# 5_Analog.net
KiCad netlist of a schematic drawn in Altium Designer
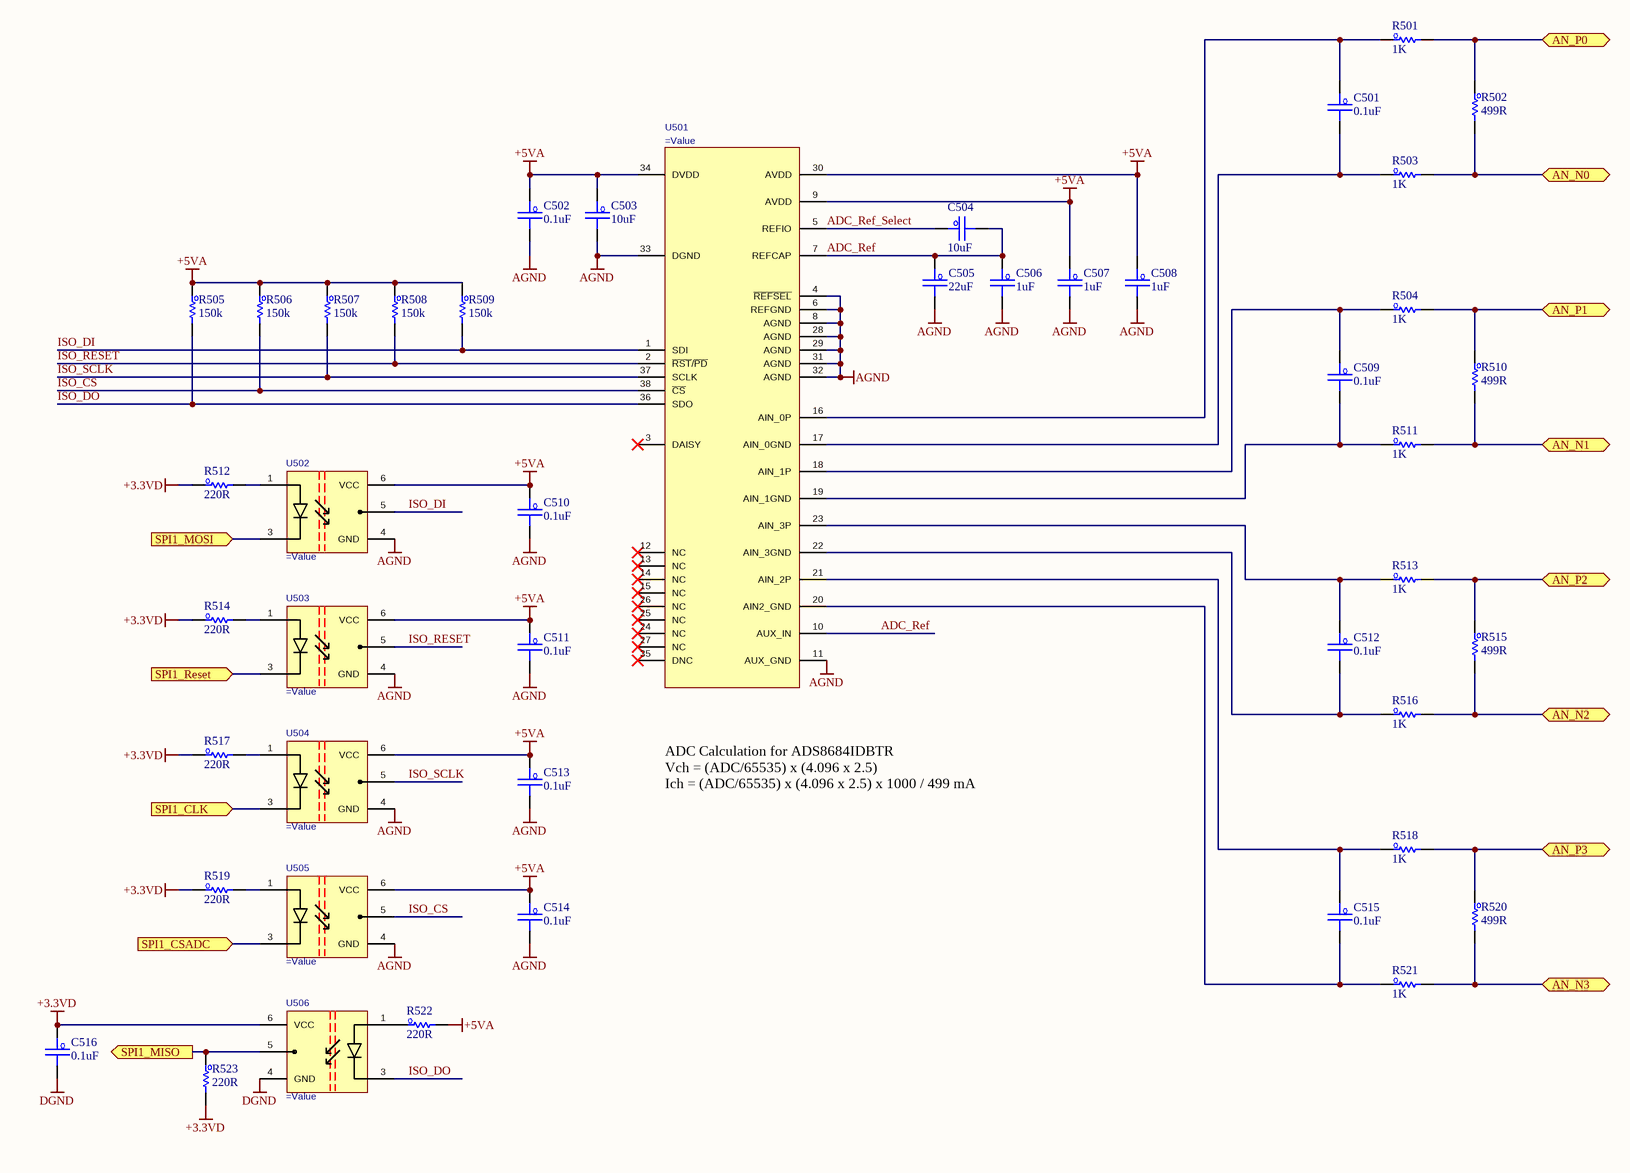
[diagram p0: 5_Analog.SchDoc]

(export (version "E")
  (design (tool "Eeschema 10.0.6"))
  (components
    (comp (ref "C501")
      (value "0.1uF")
      (footprint "C_0603")
      (description "CAP CER 0.1UF 50V X7R 0603")
      (fields (field (name "MANUFACTURER") "KEMET") (field (name "PARTNUMBER") "C0603C104K5RACTU"))
      (libsource (lib "UUSymbol") (part "C_Capacitor"))
    )
    (comp (ref "C502")
      (value "0.1uF")
      (footprint "C_0603")
      (description "CAP CER 0.1UF 50V X7R 0603")
      (fields (field (name "MANUFACTURER") "KEMET") (field (name "PARTNUMBER") "C0603C104K5RACTU"))
      (libsource (lib "UUSymbol") (part "C_Capacitor"))
    )
    (comp (ref "C503")
      (value "10uF")
      (footprint "C_0603")
      (description "CAP CER 10UF 10V X6S 0603")
      (fields
        (field (name "MANUFACTURER") "Murata Electronics")
        (field (name "PARTNUMBER") "GRT188C81A106ME13D")
      )
      (libsource (lib "UUSymbol") (part "C_Capacitor"))
    )
    (comp (ref "C504")
      (value "10uF")
      (footprint "C_0603")
      (description "CAP CER 10UF 10V X6S 0603")
      (fields
        (field (name "MANUFACTURER") "Murata Electronics")
        (field (name "PARTNUMBER") "GRT188C81A106ME13D")
      )
      (libsource (lib "UUSymbol") (part "C_Capacitor"))
    )
    (comp (ref "C505")
      (value "22uF")
      (footprint "C_0603")
      (description "CAP CER 22UF 10V X5R 0603")
      (fields
        (field (name "MANUFACTURER") "Murata Electronics")
        (field (name "PARTNUMBER") "GRM187R61A226ME15D")
      )
      (libsource (lib "UUSymbol") (part "C_Capacitor"))
    )
    (comp (ref "C506")
      (value "1uF")
      (footprint "C_0603")
      (description "CAP CER 1UF 50V X5R 0603")
      (fields
        (field (name "MANUFACTURER") "Murata Electronics")
        (field (name "PARTNUMBER") "GRT188R61H105KE13D")
      )
      (libsource (lib "UUSymbol") (part "C_Capacitor"))
    )
    (comp (ref "C507")
      (value "1uF")
      (footprint "C_0603")
      (description "CAP CER 1UF 50V X5R 0603")
      (fields
        (field (name "MANUFACTURER") "Murata Electronics")
        (field (name "PARTNUMBER") "GRT188R61H105KE13D")
      )
      (libsource (lib "UUSymbol") (part "C_Capacitor"))
    )
    (comp (ref "C508")
      (value "1uF")
      (footprint "C_0603")
      (description "CAP CER 1UF 50V X5R 0603")
      (fields
        (field (name "MANUFACTURER") "Murata Electronics")
        (field (name "PARTNUMBER") "GRT188R61H105KE13D")
      )
      (libsource (lib "UUSymbol") (part "C_Capacitor"))
    )
    (comp (ref "C509")
      (value "0.1uF")
      (footprint "C_0603")
      (description "CAP CER 0.1UF 50V X7R 0603")
      (fields (field (name "MANUFACTURER") "KEMET") (field (name "PARTNUMBER") "C0603C104K5RACTU"))
      (libsource (lib "UUSymbol") (part "C_Capacitor"))
    )
    (comp (ref "C510")
      (value "0.1uF")
      (footprint "C_0603")
      (description "CAP CER 0.1UF 50V X7R 0603")
      (fields (field (name "MANUFACTURER") "KEMET") (field (name "PARTNUMBER") "C0603C104K5RACTU"))
      (libsource (lib "UUSymbol") (part "C_Capacitor"))
    )
    (comp (ref "C511")
      (value "0.1uF")
      (footprint "C_0603")
      (description "CAP CER 0.1UF 50V X7R 0603")
      (fields (field (name "MANUFACTURER") "KEMET") (field (name "PARTNUMBER") "C0603C104K5RACTU"))
      (libsource (lib "UUSymbol") (part "C_Capacitor"))
    )
    (comp (ref "C512")
      (value "0.1uF")
      (footprint "C_0603")
      (description "CAP CER 0.1UF 50V X7R 0603")
      (fields (field (name "MANUFACTURER") "KEMET") (field (name "PARTNUMBER") "C0603C104K5RACTU"))
      (libsource (lib "UUSymbol") (part "C_Capacitor"))
    )
    (comp (ref "C513")
      (value "0.1uF")
      (footprint "C_0603")
      (description "CAP CER 0.1UF 50V X7R 0603")
      (fields (field (name "MANUFACTURER") "KEMET") (field (name "PARTNUMBER") "C0603C104K5RACTU"))
      (libsource (lib "UUSymbol") (part "C_Capacitor"))
    )
    (comp (ref "C514")
      (value "0.1uF")
      (footprint "C_0603")
      (description "CAP CER 0.1UF 50V X7R 0603")
      (fields (field (name "MANUFACTURER") "KEMET") (field (name "PARTNUMBER") "C0603C104K5RACTU"))
      (libsource (lib "UUSymbol") (part "C_Capacitor"))
    )
    (comp (ref "C515")
      (value "0.1uF")
      (footprint "C_0603")
      (description "CAP CER 0.1UF 50V X7R 0603")
      (fields (field (name "MANUFACTURER") "KEMET") (field (name "PARTNUMBER") "C0603C104K5RACTU"))
      (libsource (lib "UUSymbol") (part "C_Capacitor"))
    )
    (comp (ref "C516")
      (value "0.1uF")
      (footprint "C_0603")
      (description "CAP CER 0.1UF 50V X7R 0603")
      (fields (field (name "MANUFACTURER") "KEMET") (field (name "PARTNUMBER") "C0603C104K5RACTU"))
      (libsource (lib "UUSymbol") (part "C_Capacitor"))
    )
    (comp (ref "R501")
      (value "1K")
      (footprint "R_0603")
      (description "RES SMD 1K OHM 5% 1/10W 0603")
      (fields (field (name "MANUFACTURER") "Vishay Dale") (field (name "PARTNUMBER") "CRCW06031K00JNEA"))
      (libsource (lib "UUSymbol") (part "R_Resister"))
    )
    (comp (ref "R502")
      (value "499R")
      (footprint "R_0603")
      (description "RES SMD 499 OHM 1% 1/3W 0603")
      (fields (field (name "MANUFACTURER") "Vishay Dale") (field (name "PARTNUMBER") "CRCW0603499RFKEAHP"))
      (libsource (lib "UUSymbol") (part "R_Resister"))
    )
    (comp (ref "R503")
      (value "1K")
      (footprint "R_0603")
      (description "RES SMD 1K OHM 5% 1/10W 0603")
      (fields (field (name "MANUFACTURER") "Vishay Dale") (field (name "PARTNUMBER") "CRCW06031K00JNEA"))
      (libsource (lib "UUSymbol") (part "R_Resister"))
    )
    (comp (ref "R504")
      (value "1K")
      (footprint "R_0603")
      (description "RES SMD 1K OHM 5% 1/10W 0603")
      (fields (field (name "MANUFACTURER") "Vishay Dale") (field (name "PARTNUMBER") "CRCW06031K00JNEA"))
      (libsource (lib "UUSymbol") (part "R_Resister"))
    )
    (comp (ref "R505")
      (value "150k")
      (footprint "R_0603")
      (description "RES SMD 150K OHM 1% 1/10W 0603")
      (fields (field (name "MANUFACTURER") "Vishay Dale") (field (name "PARTNUMBER") "CRCW0603150KFKEAC"))
      (libsource (lib "UUSymbol") (part "R_Resister"))
    )
    (comp (ref "R506")
      (value "150k")
      (footprint "R_0603")
      (description "RES SMD 150K OHM 1% 1/10W 0603")
      (fields (field (name "MANUFACTURER") "Vishay Dale") (field (name "PARTNUMBER") "CRCW0603150KFKEAC"))
      (libsource (lib "UUSymbol") (part "R_Resister"))
    )
    (comp (ref "R507")
      (value "150k")
      (footprint "R_0603")
      (description "RES SMD 150K OHM 1% 1/10W 0603")
      (fields (field (name "MANUFACTURER") "Vishay Dale") (field (name "PARTNUMBER") "CRCW0603150KFKEAC"))
      (libsource (lib "UUSymbol") (part "R_Resister"))
    )
    (comp (ref "R508")
      (value "150k")
      (footprint "R_0603")
      (description "RES SMD 150K OHM 1% 1/10W 0603")
      (fields (field (name "MANUFACTURER") "Vishay Dale") (field (name "PARTNUMBER") "CRCW0603150KFKEAC"))
      (libsource (lib "UUSymbol") (part "R_Resister"))
    )
    (comp (ref "R509")
      (value "150k")
      (footprint "R_0603")
      (description "RES SMD 150K OHM 1% 1/10W 0603")
      (fields (field (name "MANUFACTURER") "Vishay Dale") (field (name "PARTNUMBER") "CRCW0603150KFKEAC"))
      (libsource (lib "UUSymbol") (part "R_Resister"))
    )
    (comp (ref "R510")
      (value "499R")
      (footprint "R_0603")
      (description "RES SMD 499 OHM 1% 1/3W 0603")
      (fields (field (name "MANUFACTURER") "Vishay Dale") (field (name "PARTNUMBER") "CRCW0603499RFKEAHP"))
      (libsource (lib "UUSymbol") (part "R_Resister"))
    )
    (comp (ref "R511")
      (value "1K")
      (footprint "R_0603")
      (description "RES SMD 1K OHM 5% 1/10W 0603")
      (fields (field (name "MANUFACTURER") "Vishay Dale") (field (name "PARTNUMBER") "CRCW06031K00JNEA"))
      (libsource (lib "UUSymbol") (part "R_Resister"))
    )
    (comp (ref "R512")
      (value "220R")
      (footprint "R_0603")
      (description "RES SMD 220 OHM 1% 1/10W 0603")
      (fields (field (name "MANUFACTURER") "Vishay Dale") (field (name "PARTNUMBER") "CRCW0603220RFKEAC"))
      (libsource (lib "UUSymbol") (part "R_Resister"))
    )
    (comp (ref "R513")
      (value "1K")
      (footprint "R_0603")
      (description "RES SMD 1K OHM 5% 1/10W 0603")
      (fields (field (name "MANUFACTURER") "Vishay Dale") (field (name "PARTNUMBER") "CRCW06031K00JNEA"))
      (libsource (lib "UUSymbol") (part "R_Resister"))
    )
    (comp (ref "R514")
      (value "220R")
      (footprint "R_0603")
      (description "RES SMD 220 OHM 1% 1/10W 0603")
      (fields (field (name "MANUFACTURER") "Vishay Dale") (field (name "PARTNUMBER") "CRCW0603220RFKEAC"))
      (libsource (lib "UUSymbol") (part "R_Resister"))
    )
    (comp (ref "R515")
      (value "499R")
      (footprint "R_0603")
      (description "RES SMD 499 OHM 1% 1/3W 0603")
      (fields (field (name "MANUFACTURER") "Vishay Dale") (field (name "PARTNUMBER") "CRCW0603499RFKEAHP"))
      (libsource (lib "UUSymbol") (part "R_Resister"))
    )
    (comp (ref "R516")
      (value "1K")
      (footprint "R_0603")
      (description "RES SMD 1K OHM 5% 1/10W 0603")
      (fields (field (name "MANUFACTURER") "Vishay Dale") (field (name "PARTNUMBER") "CRCW06031K00JNEA"))
      (libsource (lib "UUSymbol") (part "R_Resister"))
    )
    (comp (ref "R517")
      (value "220R")
      (footprint "R_0603")
      (description "RES SMD 220 OHM 1% 1/10W 0603")
      (fields (field (name "MANUFACTURER") "Vishay Dale") (field (name "PARTNUMBER") "CRCW0603220RFKEAC"))
      (libsource (lib "UUSymbol") (part "R_Resister"))
    )
    (comp (ref "R518")
      (value "1K")
      (footprint "R_0603")
      (description "RES SMD 1K OHM 5% 1/10W 0603")
      (fields (field (name "MANUFACTURER") "Vishay Dale") (field (name "PARTNUMBER") "CRCW06031K00JNEA"))
      (libsource (lib "UUSymbol") (part "R_Resister"))
    )
    (comp (ref "R519")
      (value "220R")
      (footprint "R_0603")
      (description "RES SMD 220 OHM 1% 1/10W 0603")
      (fields (field (name "MANUFACTURER") "Vishay Dale") (field (name "PARTNUMBER") "CRCW0603220RFKEAC"))
      (libsource (lib "UUSymbol") (part "R_Resister"))
    )
    (comp (ref "R520")
      (value "499R")
      (footprint "R_0603")
      (description "RES SMD 499 OHM 1% 1/3W 0603")
      (fields (field (name "MANUFACTURER") "Vishay Dale") (field (name "PARTNUMBER") "CRCW0603499RFKEAHP"))
      (libsource (lib "UUSymbol") (part "R_Resister"))
    )
    (comp (ref "R521")
      (value "1K")
      (footprint "R_0603")
      (description "RES SMD 1K OHM 5% 1/10W 0603")
      (fields (field (name "MANUFACTURER") "Vishay Dale") (field (name "PARTNUMBER") "CRCW06031K00JNEA"))
      (libsource (lib "UUSymbol") (part "R_Resister"))
    )
    (comp (ref "R522")
      (value "220R")
      (footprint "R_0603")
      (description "RES SMD 220 OHM 1% 1/10W 0603")
      (fields (field (name "MANUFACTURER") "Vishay Dale") (field (name "PARTNUMBER") "CRCW0603220RFKEAC"))
      (libsource (lib "UUSymbol") (part "R_Resister"))
    )
    (comp (ref "R523")
      (value "220R")
      (footprint "R_0603")
      (description "RES SMD 220 OHM 1% 1/10W 0603")
      (fields (field (name "MANUFACTURER") "Vishay Dale") (field (name "PARTNUMBER") "CRCW0603220RFKEAC"))
      (libsource (lib "UUSymbol") (part "R_Resister"))
    )
    (comp (ref "U501")
      (value "~")
      (footprint "DBT0038A_N_TEX")
      (description "IC ADC 16BIT SAR 38TSSOP")
      (fields (field (name "MANUFACTURER") "Texas Instruments") (field (name "PARTNUMBER") "ADS8684IDBTR"))
      (libsource (lib "UUSymbol") (part "IC_ADC_ADS8684IDBTR"))
    )
    (comp (ref "U502")
      (value "~")
      (footprint "5PIN SO6_TOS")
      (description "OPTOISO 5KV PUSH PULL SO6L")
      (fields
        (field (name "MANUFACTURER") "Toshiba Semiconductor and Storage")
        (field (name "PARTNUMBER") "TLP109(TPR,E)")
      )
      (libsource (lib "UUSymbol") (part "IC_OPTO_TLP109(TPR,E)"))
    )
    (comp (ref "U503")
      (value "~")
      (footprint "5PIN SO6_TOS")
      (description "OPTOISO 5KV PUSH PULL SO6L")
      (fields
        (field (name "MANUFACTURER") "Toshiba Semiconductor and Storage")
        (field (name "PARTNUMBER") "TLP109(TPR,E)")
      )
      (libsource (lib "UUSymbol") (part "IC_OPTO_TLP109(TPR,E)"))
    )
    (comp (ref "U504")
      (value "~")
      (footprint "5PIN SO6_TOS")
      (description "OPTOISO 5KV PUSH PULL SO6L")
      (fields
        (field (name "MANUFACTURER") "Toshiba Semiconductor and Storage")
        (field (name "PARTNUMBER") "TLP109(TPR,E)")
      )
      (libsource (lib "UUSymbol") (part "IC_OPTO_TLP109(TPR,E)"))
    )
    (comp (ref "U505")
      (value "~")
      (footprint "5PIN SO6_TOS")
      (description "OPTOISO 5KV PUSH PULL SO6L")
      (fields
        (field (name "MANUFACTURER") "Toshiba Semiconductor and Storage")
        (field (name "PARTNUMBER") "TLP109(TPR,E)")
      )
      (libsource (lib "UUSymbol") (part "IC_OPTO_TLP109(TPR,E)"))
    )
    (comp (ref "U506")
      (value "~")
      (footprint "5PIN SO6_TOS")
      (description "OPTOISO 5KV PUSH PULL SO6L")
      (fields
        (field (name "MANUFACTURER") "Toshiba Semiconductor and Storage")
        (field (name "PARTNUMBER") "TLP109(TPR,E)")
      )
      (libsource (lib "") (part "IC_OPTO_TLP109(TPR,E)_1"))
    )
  )
  (nets
    (net (code "1") (name "+3.3VD") (class "Default")
      (node (ref "C516") (pin "1") (pinfunction "1_1") (pintype "passive"))
      (node (ref "R512") (pin "1") (pinfunction "1_1") (pintype "passive"))
      (node (ref "R514") (pin "1") (pinfunction "1_1") (pintype "passive"))
      (node (ref "R517") (pin "1") (pinfunction "1_1") (pintype "passive"))
      (node (ref "R519") (pin "1") (pinfunction "1_1") (pintype "passive"))
      (node (ref "R523") (pin "2") (pinfunction "2_2") (pintype "passive"))
      (node (ref "U506") (pin "6") (pinfunction "VCC_6") (pintype "passive"))
    )
    (net (code "2") (name "+5VA") (class "Default")
      (node (ref "C502") (pin "1") (pinfunction "1_1") (pintype "passive"))
      (node (ref "C503") (pin "1") (pinfunction "1_1") (pintype "passive"))
      (node (ref "C507") (pin "1") (pinfunction "1_1") (pintype "passive"))
      (node (ref "C508") (pin "1") (pinfunction "1_1") (pintype "passive"))
      (node (ref "C510") (pin "1") (pinfunction "1_1") (pintype "passive"))
      (node (ref "C511") (pin "1") (pinfunction "1_1") (pintype "passive"))
      (node (ref "C513") (pin "1") (pinfunction "1_1") (pintype "passive"))
      (node (ref "C514") (pin "1") (pinfunction "1_1") (pintype "passive"))
      (node (ref "R505") (pin "1") (pinfunction "1_1") (pintype "passive"))
      (node (ref "R506") (pin "1") (pinfunction "1_1") (pintype "passive"))
      (node (ref "R507") (pin "1") (pinfunction "1_1") (pintype "passive"))
      (node (ref "R508") (pin "1") (pinfunction "1_1") (pintype "passive"))
      (node (ref "R509") (pin "1") (pinfunction "1_1") (pintype "passive"))
      (node (ref "R522") (pin "2") (pinfunction "2_2") (pintype "passive"))
      (node (ref "U501") (pin "30") (pinfunction "AVDD_30") (pintype "passive"))
      (node (ref "U501") (pin "34") (pinfunction "DVDD_34") (pintype "passive"))
      (node (ref "U501") (pin "9") (pinfunction "AVDD_9") (pintype "passive"))
      (node (ref "U502") (pin "6") (pinfunction "VCC_6") (pintype "passive"))
      (node (ref "U503") (pin "6") (pinfunction "VCC_6") (pintype "passive"))
      (node (ref "U504") (pin "6") (pinfunction "VCC_6") (pintype "passive"))
      (node (ref "U505") (pin "6") (pinfunction "VCC_6") (pintype "passive"))
    )
    (net (code "3") (name "/ADC_Ref") (class "Default")
      (node (ref "C504") (pin "2") (pinfunction "2_2") (pintype "passive"))
      (node (ref "C505") (pin "1") (pinfunction "1_1") (pintype "passive"))
      (node (ref "C506") (pin "1") (pinfunction "1_1") (pintype "passive"))
      (node (ref "U501") (pin "10") (pinfunction "AUX_IN_10") (pintype "passive"))
      (node (ref "U501") (pin "7") (pinfunction "REFCAP_7") (pintype "passive"))
    )
    (net (code "4") (name "/ADC_Ref_Select") (class "Default")
      (node (ref "C504") (pin "1") (pinfunction "1_1") (pintype "passive"))
      (node (ref "U501") (pin "5") (pinfunction "REFIO_5") (pintype "passive"))
    )
    (net (code "5") (name "/AN_N0") (class "Default")
      (node (ref "R502") (pin "2") (pinfunction "2_2") (pintype "passive"))
      (node (ref "R503") (pin "2") (pinfunction "2_2") (pintype "passive"))
    )
    (net (code "6") (name "/AN_N1") (class "Default")
      (node (ref "R510") (pin "2") (pinfunction "2_2") (pintype "passive"))
      (node (ref "R511") (pin "2") (pinfunction "2_2") (pintype "passive"))
    )
    (net (code "7") (name "/AN_N2") (class "Default")
      (node (ref "R515") (pin "2") (pinfunction "2_2") (pintype "passive"))
      (node (ref "R516") (pin "2") (pinfunction "2_2") (pintype "passive"))
    )
    (net (code "8") (name "/AN_N3") (class "Default")
      (node (ref "R520") (pin "2") (pinfunction "2_2") (pintype "passive"))
      (node (ref "R521") (pin "2") (pinfunction "2_2") (pintype "passive"))
    )
    (net (code "9") (name "/AN_P0") (class "Default")
      (node (ref "R501") (pin "2") (pinfunction "2_2") (pintype "passive"))
      (node (ref "R502") (pin "1") (pinfunction "1_1") (pintype "passive"))
    )
    (net (code "10") (name "/AN_P1") (class "Default")
      (node (ref "R504") (pin "2") (pinfunction "2_2") (pintype "passive"))
      (node (ref "R510") (pin "1") (pinfunction "1_1") (pintype "passive"))
    )
    (net (code "11") (name "/AN_P2") (class "Default")
      (node (ref "R513") (pin "2") (pinfunction "2_2") (pintype "passive"))
      (node (ref "R515") (pin "1") (pinfunction "1_1") (pintype "passive"))
    )
    (net (code "12") (name "/AN_P3") (class "Default")
      (node (ref "R518") (pin "2") (pinfunction "2_2") (pintype "passive"))
      (node (ref "R520") (pin "1") (pinfunction "1_1") (pintype "passive"))
    )
    (net (code "13") (name "/ISO_CS") (class "Default")
      (node (ref "R506") (pin "2") (pinfunction "2_2") (pintype "passive"))
      (node (ref "U501") (pin "38") (pinfunction "~{CS}_38") (pintype "passive"))
      (node (ref "U505") (pin "5") (pinfunction "O1_5") (pintype "passive"))
    )
    (net (code "14") (name "/ISO_DI") (class "Default")
      (node (ref "R509") (pin "2") (pinfunction "2_2") (pintype "passive"))
      (node (ref "U501") (pin "1") (pinfunction "SDI_1") (pintype "passive"))
      (node (ref "U502") (pin "5") (pinfunction "O1_5") (pintype "passive"))
    )
    (net (code "15") (name "/ISO_DO") (class "Default")
      (node (ref "R505") (pin "2") (pinfunction "2_2") (pintype "passive"))
      (node (ref "U501") (pin "36") (pinfunction "SDO_36") (pintype "passive"))
      (node (ref "U506") (pin "3") (pinfunction "A_3") (pintype "passive"))
    )
    (net (code "16") (name "/ISO_RESET") (class "Default")
      (node (ref "R508") (pin "2") (pinfunction "2_2") (pintype "passive"))
      (node (ref "U501") (pin "2") (pinfunction "~{RST}/~{PD}_2") (pintype "passive"))
      (node (ref "U503") (pin "5") (pinfunction "O1_5") (pintype "passive"))
    )
    (net (code "17") (name "/ISO_SCLK") (class "Default")
      (node (ref "R507") (pin "2") (pinfunction "2_2") (pintype "passive"))
      (node (ref "U501") (pin "37") (pinfunction "SCLK_37") (pintype "passive"))
      (node (ref "U504") (pin "5") (pinfunction "O1_5") (pintype "passive"))
    )
    (net (code "18") (name "/SPI1_CLK") (class "Default")
      (node (ref "U504") (pin "3") (pinfunction "A_3") (pintype "passive"))
    )
    (net (code "19") (name "/SPI1_CSADC") (class "Default")
      (node (ref "U505") (pin "3") (pinfunction "A_3") (pintype "passive"))
    )
    (net (code "20") (name "/SPI1_MISO") (class "Default")
      (node (ref "R523") (pin "1") (pinfunction "1_1") (pintype "passive"))
      (node (ref "U506") (pin "5") (pinfunction "O1_5") (pintype "passive"))
    )
    (net (code "21") (name "/SPI1_MOSI") (class "Default")
      (node (ref "U502") (pin "3") (pinfunction "A_3") (pintype "passive"))
    )
    (net (code "22") (name "/SPI1_Reset") (class "Default")
      (node (ref "U503") (pin "3") (pinfunction "A_3") (pintype "passive"))
    )
    (net (code "23") (name "AGND") (class "Default")
      (node (ref "C502") (pin "2") (pinfunction "2_2") (pintype "passive"))
      (node (ref "C503") (pin "2") (pinfunction "2_2") (pintype "passive"))
      (node (ref "C505") (pin "2") (pinfunction "2_2") (pintype "passive"))
      (node (ref "C506") (pin "2") (pinfunction "2_2") (pintype "passive"))
      (node (ref "C507") (pin "2") (pinfunction "2_2") (pintype "passive"))
      (node (ref "C508") (pin "2") (pinfunction "2_2") (pintype "passive"))
      (node (ref "C510") (pin "2") (pinfunction "2_2") (pintype "passive"))
      (node (ref "C511") (pin "2") (pinfunction "2_2") (pintype "passive"))
      (node (ref "C513") (pin "2") (pinfunction "2_2") (pintype "passive"))
      (node (ref "C514") (pin "2") (pinfunction "2_2") (pintype "passive"))
      (node (ref "U501") (pin "11") (pinfunction "AUX_GND_11") (pintype "passive"))
      (node (ref "U501") (pin "28") (pinfunction "AGND_28") (pintype "passive"))
      (node (ref "U501") (pin "29") (pinfunction "AGND_29") (pintype "passive"))
      (node (ref "U501") (pin "31") (pinfunction "AGND_31") (pintype "passive"))
      (node (ref "U501") (pin "32") (pinfunction "AGND_32") (pintype "passive"))
      (node (ref "U501") (pin "33") (pinfunction "DGND_33") (pintype "passive"))
      (node (ref "U501") (pin "4") (pinfunction "~{REFSEL}_4") (pintype "passive"))
      (node (ref "U501") (pin "6") (pinfunction "REFGND_6") (pintype "passive"))
      (node (ref "U501") (pin "8") (pinfunction "AGND_8") (pintype "passive"))
      (node (ref "U502") (pin "4") (pinfunction "GND_4") (pintype "passive"))
      (node (ref "U503") (pin "4") (pinfunction "GND_4") (pintype "passive"))
      (node (ref "U504") (pin "4") (pinfunction "GND_4") (pintype "passive"))
      (node (ref "U505") (pin "4") (pinfunction "GND_4") (pintype "passive"))
    )
    (net (code "24") (name "DGND") (class "Default")
      (node (ref "C516") (pin "2") (pinfunction "2_2") (pintype "passive"))
      (node (ref "U506") (pin "4") (pinfunction "GND_4") (pintype "passive"))
    )
    (net (code "25") (name "Net-(R512-Pad2)") (class "Default")
      (node (ref "R512") (pin "2") (pinfunction "2_2") (pintype "passive"))
      (node (ref "U502") (pin "1") (pinfunction "A_1") (pintype "passive"))
    )
    (net (code "26") (name "Net-(R514-Pad2)") (class "Default")
      (node (ref "R514") (pin "2") (pinfunction "2_2") (pintype "passive"))
      (node (ref "U503") (pin "1") (pinfunction "A_1") (pintype "passive"))
    )
    (net (code "27") (name "Net-(R517-Pad2)") (class "Default")
      (node (ref "R517") (pin "2") (pinfunction "2_2") (pintype "passive"))
      (node (ref "U504") (pin "1") (pinfunction "A_1") (pintype "passive"))
    )
    (net (code "28") (name "Net-(R519-Pad2)") (class "Default")
      (node (ref "R519") (pin "2") (pinfunction "2_2") (pintype "passive"))
      (node (ref "U505") (pin "1") (pinfunction "A_1") (pintype "passive"))
    )
    (net (code "29") (name "Net-(R522-Pad1)") (class "Default")
      (node (ref "R522") (pin "1") (pinfunction "1_1") (pintype "passive"))
      (node (ref "U506") (pin "1") (pinfunction "A_1") (pintype "passive"))
    )
    (net (code "30") (name "Net-(U501-AIN2_GND)") (class "Default")
      (node (ref "C515") (pin "2") (pinfunction "2_2") (pintype "passive"))
      (node (ref "R521") (pin "1") (pinfunction "1_1") (pintype "passive"))
      (node (ref "U501") (pin "20") (pinfunction "AIN2_GND_20") (pintype "passive"))
    )
    (net (code "31") (name "Net-(U501-AIN_0GND)") (class "Default")
      (node (ref "C501") (pin "2") (pinfunction "2_2") (pintype "passive"))
      (node (ref "R503") (pin "1") (pinfunction "1_1") (pintype "passive"))
      (node (ref "U501") (pin "17") (pinfunction "AIN_0GND_17") (pintype "passive"))
    )
    (net (code "32") (name "Net-(U501-AIN_0P)") (class "Default")
      (node (ref "C501") (pin "1") (pinfunction "1_1") (pintype "passive"))
      (node (ref "R501") (pin "1") (pinfunction "1_1") (pintype "passive"))
      (node (ref "U501") (pin "16") (pinfunction "AIN_0P_16") (pintype "passive"))
    )
    (net (code "33") (name "Net-(U501-AIN_1GND)") (class "Default")
      (node (ref "C509") (pin "2") (pinfunction "2_2") (pintype "passive"))
      (node (ref "R511") (pin "1") (pinfunction "1_1") (pintype "passive"))
      (node (ref "U501") (pin "19") (pinfunction "AIN_1GND_19") (pintype "passive"))
    )
    (net (code "34") (name "Net-(U501-AIN_1P)") (class "Default")
      (node (ref "C509") (pin "1") (pinfunction "1_1") (pintype "passive"))
      (node (ref "R504") (pin "1") (pinfunction "1_1") (pintype "passive"))
      (node (ref "U501") (pin "18") (pinfunction "AIN_1P_18") (pintype "passive"))
    )
    (net (code "35") (name "Net-(U501-AIN_2P)") (class "Default")
      (node (ref "C515") (pin "1") (pinfunction "1_1") (pintype "passive"))
      (node (ref "R518") (pin "1") (pinfunction "1_1") (pintype "passive"))
      (node (ref "U501") (pin "21") (pinfunction "AIN_2P_21") (pintype "passive"))
    )
    (net (code "36") (name "Net-(U501-AIN_3GND)") (class "Default")
      (node (ref "C512") (pin "2") (pinfunction "2_2") (pintype "passive"))
      (node (ref "R516") (pin "1") (pinfunction "1_1") (pintype "passive"))
      (node (ref "U501") (pin "22") (pinfunction "AIN_3GND_22") (pintype "passive"))
    )
    (net (code "37") (name "Net-(U501-AIN_3P)") (class "Default")
      (node (ref "C512") (pin "1") (pinfunction "1_1") (pintype "passive"))
      (node (ref "R513") (pin "1") (pinfunction "1_1") (pintype "passive"))
      (node (ref "U501") (pin "23") (pinfunction "AIN_3P_23") (pintype "passive"))
    )
    (net (code "38") (name "unconnected-(U501-DAISY-Pad3)") (class "Default")
      (node (ref "U501") (pin "3") (pinfunction "DAISY_3") (pintype "passive+no_connect"))
    )
    (net (code "39") (name "unconnected-(U501-DNC-Pad35)") (class "Default")
      (node (ref "U501") (pin "35") (pinfunction "DNC_35") (pintype "passive+no_connect"))
    )
    (net (code "40") (name "unconnected-(U501-NC-Pad12)") (class "Default")
      (node (ref "U501") (pin "12") (pinfunction "NC_12") (pintype "passive+no_connect"))
    )
    (net (code "41") (name "unconnected-(U501-NC-Pad13)") (class "Default")
      (node (ref "U501") (pin "13") (pinfunction "NC_13") (pintype "passive+no_connect"))
    )
    (net (code "42") (name "unconnected-(U501-NC-Pad14)") (class "Default")
      (node (ref "U501") (pin "14") (pinfunction "NC_14") (pintype "passive+no_connect"))
    )
    (net (code "43") (name "unconnected-(U501-NC-Pad15)") (class "Default")
      (node (ref "U501") (pin "15") (pinfunction "NC_15") (pintype "passive+no_connect"))
    )
    (net (code "44") (name "unconnected-(U501-NC-Pad24)") (class "Default")
      (node (ref "U501") (pin "24") (pinfunction "NC_24") (pintype "passive+no_connect"))
    )
    (net (code "45") (name "unconnected-(U501-NC-Pad25)") (class "Default")
      (node (ref "U501") (pin "25") (pinfunction "NC_25") (pintype "passive+no_connect"))
    )
    (net (code "46") (name "unconnected-(U501-NC-Pad26)") (class "Default")
      (node (ref "U501") (pin "26") (pinfunction "NC_26") (pintype "passive+no_connect"))
    )
    (net (code "47") (name "unconnected-(U501-NC-Pad27)") (class "Default")
      (node (ref "U501") (pin "27") (pinfunction "NC_27") (pintype "passive+no_connect"))
    )
  )
)
